# MainBoard1_3.net
KiCad netlist of a schematic drawn in EAGLE
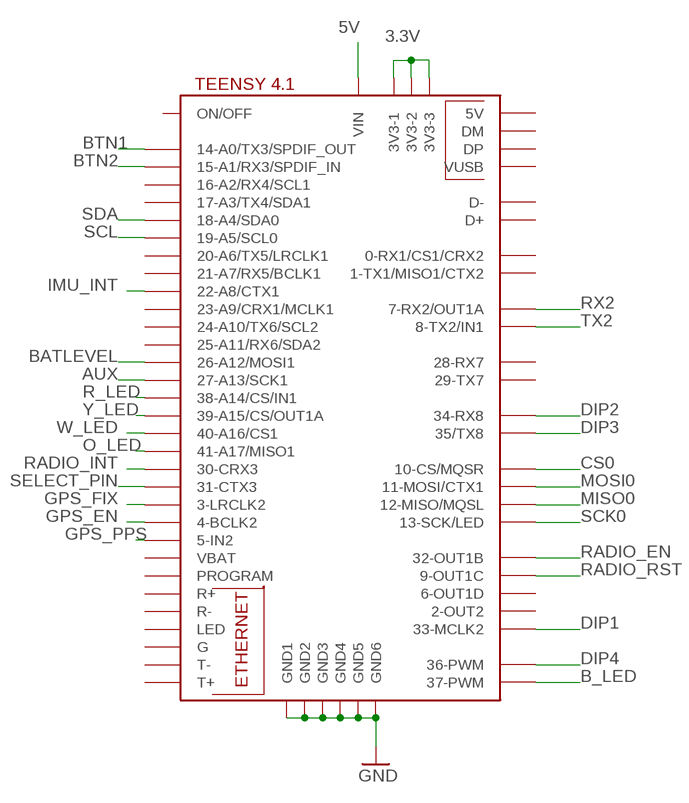
[diagram p0: schematic, sheet 1]
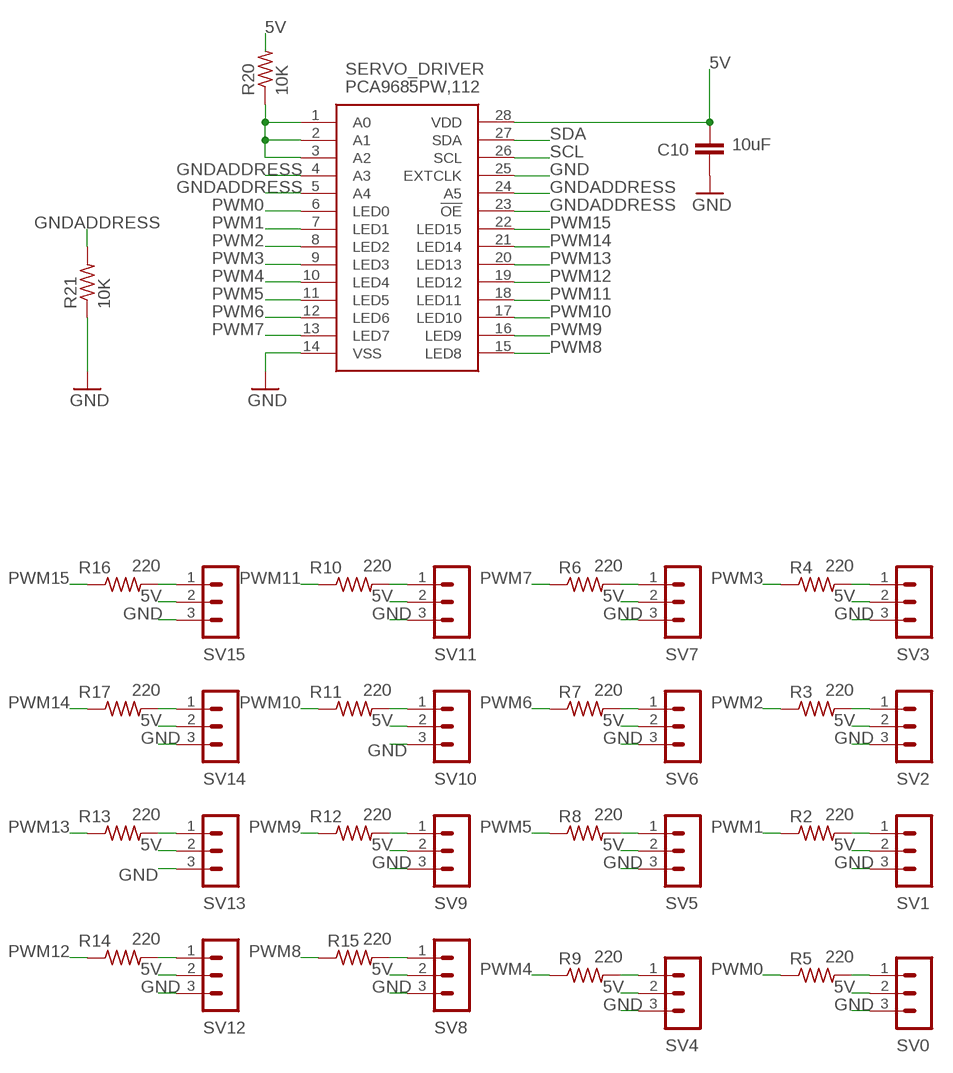
[diagram p1: schematic, sheet 2]
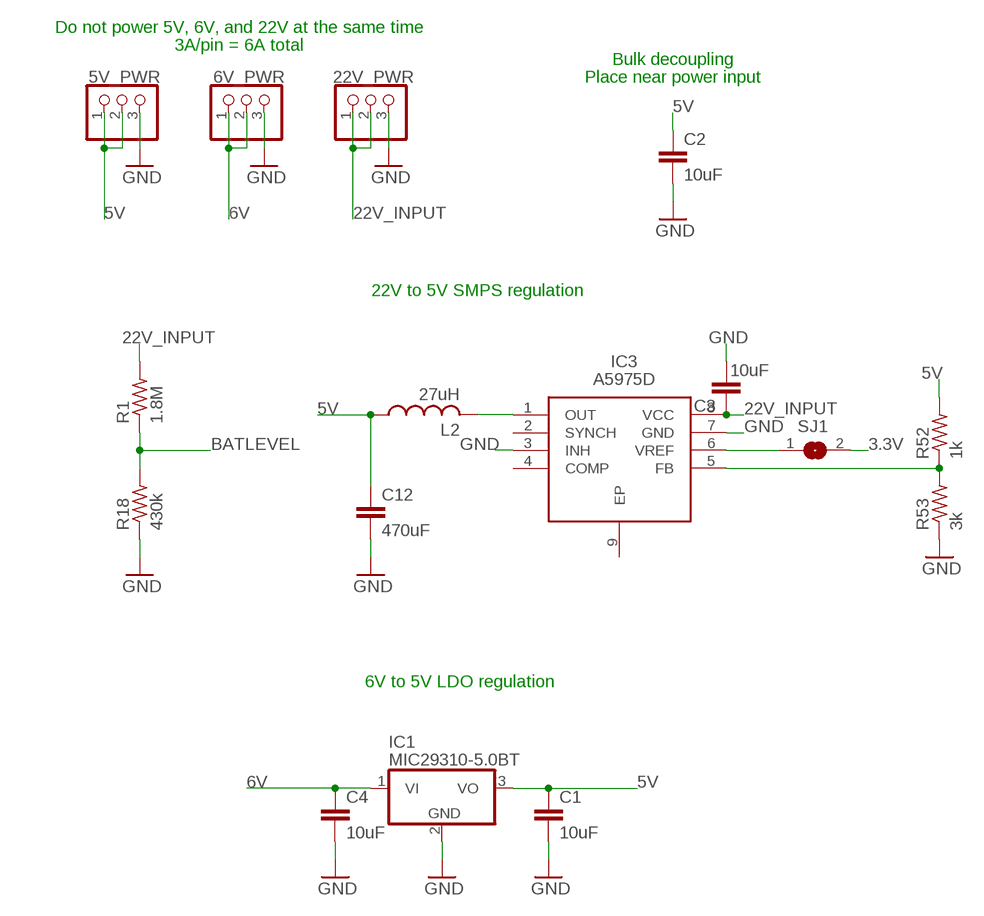
[diagram p2: schematic, sheet 3]
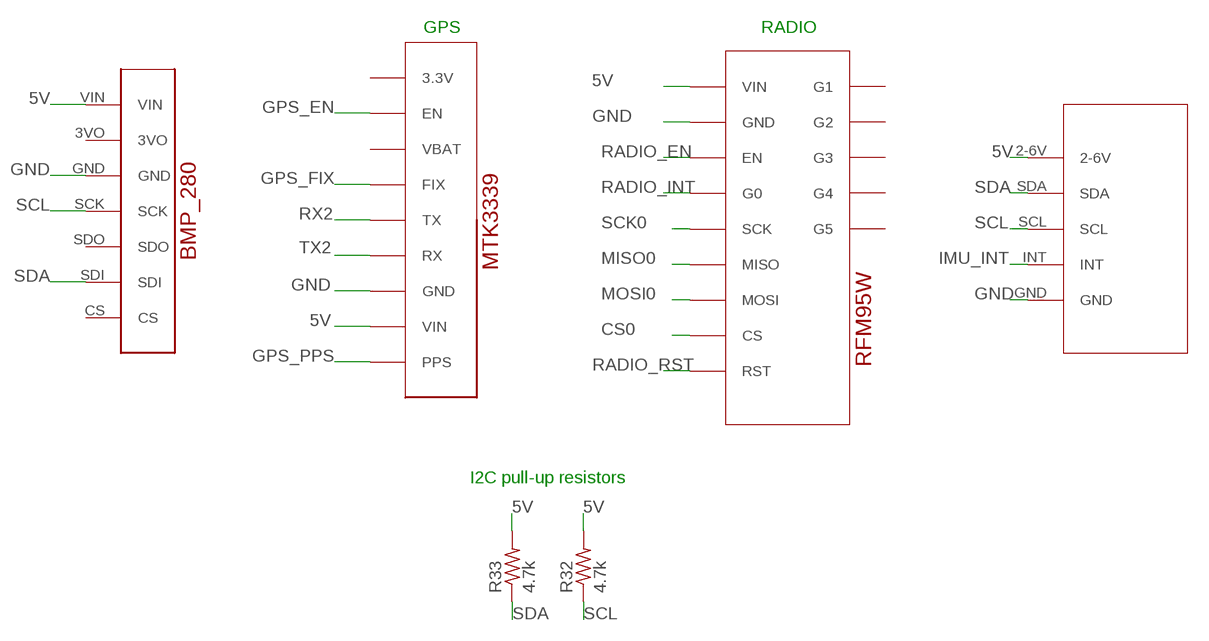
[diagram p3: schematic, sheet 4]
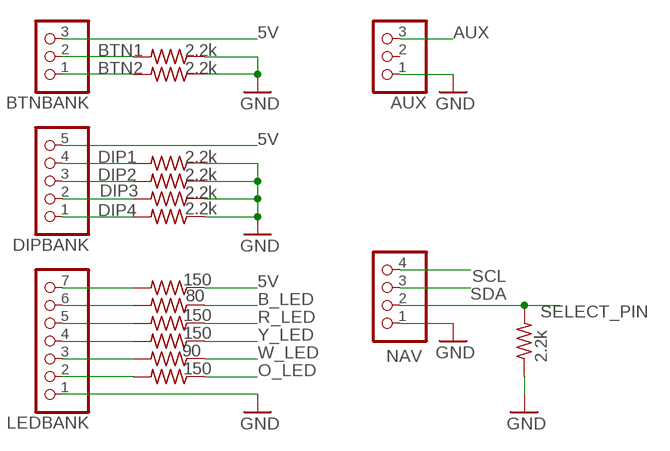
[diagram p4: schematic, sheet 5]
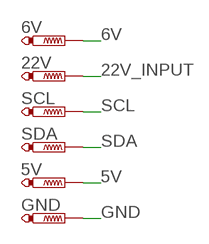
[diagram p5: schematic, sheet 6]

(export (version "E")
  (design (tool "Eeschema 10.0.6"))
  (components
    (comp (ref "5V")
      (value "PTR1B1,27")
      (footprint "eagle-import:B1,27")
      (libsource (lib "eagle-import") (part "PTR1B1,27"))
    )
    (comp (ref "6V")
      (value "PTR1B1,27")
      (footprint "eagle-import:B1,27")
      (libsource (lib "eagle-import") (part "PTR1B1,27"))
    )
    (comp (ref "22V")
      (value "PTR1B1,27")
      (footprint "eagle-import:B1,27")
      (libsource (lib "eagle-import") (part "PTR1B1,27"))
    )
    (comp (ref "GND")
      (value "PTR1B1,27")
      (footprint "eagle-import:B1,27")
      (libsource (lib "eagle-import") (part "PTR1B1,27"))
    )
    (comp (ref "SCL")
      (value "PTR1B1,27")
      (footprint "eagle-import:B1,27")
      (libsource (lib "eagle-import") (part "PTR1B1,27"))
    )
    (comp (ref "SDA")
      (value "PTR1B1,27")
      (footprint "eagle-import:B1,27")
      (libsource (lib "eagle-import") (part "PTR1B1,27"))
    )
    (comp (ref "C10")
      (value "10uF")
      (footprint "eagle-import:C2.5-3")
      (libsource (lib "eagle-import") (part "C2,5-3"))
    )
    (comp (ref "R2")
      (value "220")
      (footprint "eagle-import:0204_7")
      (libsource (lib "eagle-import") (part "R-US_0204/7"))
    )
    (comp (ref "R3")
      (value "220")
      (footprint "eagle-import:0204_7")
      (libsource (lib "eagle-import") (part "R-US_0204/7"))
    )
    (comp (ref "R4")
      (value "220")
      (footprint "eagle-import:0204_7")
      (libsource (lib "eagle-import") (part "R-US_0204/7"))
    )
    (comp (ref "R5")
      (value "220")
      (footprint "eagle-import:0204_7")
      (libsource (lib "eagle-import") (part "R-US_0204/7"))
    )
    (comp (ref "R6")
      (value "220")
      (footprint "eagle-import:0204_7")
      (libsource (lib "eagle-import") (part "R-US_0204/7"))
    )
    (comp (ref "R7")
      (value "220")
      (footprint "eagle-import:0204_7")
      (libsource (lib "eagle-import") (part "R-US_0204/7"))
    )
    (comp (ref "R8")
      (value "220")
      (footprint "eagle-import:0204_7")
      (libsource (lib "eagle-import") (part "R-US_0204/7"))
    )
    (comp (ref "R9")
      (value "220")
      (footprint "eagle-import:0204_7")
      (libsource (lib "eagle-import") (part "R-US_0204/7"))
    )
    (comp (ref "R10")
      (value "220")
      (footprint "eagle-import:0204_7")
      (libsource (lib "eagle-import") (part "R-US_0204/7"))
    )
    (comp (ref "R11")
      (value "220")
      (footprint "eagle-import:0204_7")
      (libsource (lib "eagle-import") (part "R-US_0204/7"))
    )
    (comp (ref "R12")
      (value "220")
      (footprint "eagle-import:0204_7")
      (libsource (lib "eagle-import") (part "R-US_0204/7"))
    )
    (comp (ref "R13")
      (value "220")
      (footprint "eagle-import:0204_7")
      (libsource (lib "eagle-import") (part "R-US_0204/7"))
    )
    (comp (ref "R14")
      (value "220")
      (footprint "eagle-import:0204_7")
      (libsource (lib "eagle-import") (part "R-US_0204/7"))
    )
    (comp (ref "R15")
      (value "220")
      (footprint "eagle-import:0204_7")
      (libsource (lib "eagle-import") (part "R-US_0204/7"))
    )
    (comp (ref "R16")
      (value "220")
      (footprint "eagle-import:0204_7")
      (libsource (lib "eagle-import") (part "R-US_0204/7"))
    )
    (comp (ref "R17")
      (value "220")
      (footprint "eagle-import:0204_7")
      (libsource (lib "eagle-import") (part "R-US_0204/7"))
    )
    (comp (ref "R20")
      (value "10K")
      (footprint "eagle-import:0204_7")
      (libsource (lib "eagle-import") (part "R-US_0204/7"))
    )
    (comp (ref "R21")
      (value "10K")
      (footprint "eagle-import:0204_7")
      (libsource (lib "eagle-import") (part "R-US_0204/7"))
    )
    (comp (ref "SERVO_DRIVER")
      (value "PCA9685PW,112")
      (footprint "eagle-import:SOP65P640X110-28N")
      (fields (field (name "MOUSER_PART_NUMBER") "771-PCA9685PW,112"))
      (libsource (lib "eagle-import") (part "PCA9685PW,112"))
    )
    (comp (ref "SV0")
      (value "MA03-1")
      (footprint "eagle-import:MA03-1")
      (libsource (lib "eagle-import") (part "MA03-1"))
    )
    (comp (ref "SV1")
      (value "MA03-1")
      (footprint "eagle-import:MA03-1")
      (libsource (lib "eagle-import") (part "MA03-1"))
    )
    (comp (ref "SV2")
      (value "MA03-1")
      (footprint "eagle-import:MA03-1")
      (libsource (lib "eagle-import") (part "MA03-1"))
    )
    (comp (ref "SV3")
      (value "MA03-1")
      (footprint "eagle-import:MA03-1")
      (libsource (lib "eagle-import") (part "MA03-1"))
    )
    (comp (ref "SV4")
      (value "MA03-1")
      (footprint "eagle-import:MA03-1")
      (libsource (lib "eagle-import") (part "MA03-1"))
    )
    (comp (ref "SV5")
      (value "MA03-1")
      (footprint "eagle-import:MA03-1")
      (libsource (lib "eagle-import") (part "MA03-1"))
    )
    (comp (ref "SV6")
      (value "MA03-1")
      (footprint "eagle-import:MA03-1")
      (libsource (lib "eagle-import") (part "MA03-1"))
    )
    (comp (ref "SV7")
      (value "MA03-1")
      (footprint "eagle-import:MA03-1")
      (libsource (lib "eagle-import") (part "MA03-1"))
    )
    (comp (ref "SV8")
      (value "MA03-1")
      (footprint "eagle-import:MA03-1")
      (libsource (lib "eagle-import") (part "MA03-1"))
    )
    (comp (ref "SV9")
      (value "MA03-1")
      (footprint "eagle-import:MA03-1")
      (libsource (lib "eagle-import") (part "MA03-1"))
    )
    (comp (ref "SV10")
      (value "MA03-1")
      (footprint "eagle-import:MA03-1")
      (libsource (lib "eagle-import") (part "MA03-1"))
    )
    (comp (ref "SV11")
      (value "MA03-1")
      (footprint "eagle-import:MA03-1")
      (libsource (lib "eagle-import") (part "MA03-1"))
    )
    (comp (ref "SV12")
      (value "MA03-1")
      (footprint "eagle-import:MA03-1")
      (libsource (lib "eagle-import") (part "MA03-1"))
    )
    (comp (ref "SV13")
      (value "MA03-1")
      (footprint "eagle-import:MA03-1")
      (libsource (lib "eagle-import") (part "MA03-1"))
    )
    (comp (ref "SV14")
      (value "MA03-1")
      (footprint "eagle-import:MA03-1")
      (libsource (lib "eagle-import") (part "MA03-1"))
    )
    (comp (ref "SV15")
      (value "MA03-1")
      (footprint "eagle-import:MA03-1")
      (libsource (lib "eagle-import") (part "MA03-1"))
    )
    (comp (ref "GPSMTK3339")
      (value "ADAFRUIT_MTK3339_GPS")
      (footprint "eagle-import:ADAFRUIT_MTK3339_GPS")
      (libsource (lib "eagle-import") (part "ADAFRUIT_MTK3339_GPS"))
    )
    (comp (ref "IMU")
      (value "ICM20948BREAKOUTDEVICE")
      (footprint "eagle-import:ICM20948BREAKOUT")
      (fields (field (name "SPICEPREFIX") "X"))
      (libsource (lib "eagle-import") (part "ICM20948BREAKOUTDEVICE"))
    )
    (comp (ref "R32")
      (value "4.7k")
      (footprint "eagle-import:0204_7")
      (libsource (lib "eagle-import") (part "R-US_0204/7"))
    )
    (comp (ref "R33")
      (value "4.7k")
      (footprint "eagle-import:0204_7")
      (libsource (lib "eagle-import") (part "R-US_0204/7"))
    )
    (comp (ref "RADIO")
      (value "ADAFRUIT_RFM95W_LORA_RADIO")
      (footprint "eagle-import:ADAFRUIT_RFM95W_LORA_RADIO")
      (libsource (lib "eagle-import") (part "ADAFRUIT_RFM95W_LORA_RADIO"))
    )
    (comp (ref "U1")
      (value "ADAFRUIT_BMP280_BAROMETER")
      (footprint "eagle-import:ADAFRUIT_BMP280_BAROMETER")
      (libsource (lib "eagle-import") (part "ADAFRUIT_BMP280_BAROMETER"))
    )
    (comp (ref "5V_PWR")
      (value "5V_PWR")
      (footprint "eagle-import:1X03")
      (libsource (lib "eagle-import") (part "PINHD-1X3"))
    )
    (comp (ref "6V_PWR")
      (value "6V_PWR")
      (footprint "eagle-import:1X03")
      (libsource (lib "eagle-import") (part "PINHD-1X3"))
    )
    (comp (ref "22V_PWR")
      (value "22V_PWR")
      (footprint "eagle-import:1X03")
      (libsource (lib "eagle-import") (part "PINHD-1X3"))
    )
    (comp (ref "C1")
      (value "10uF")
      (footprint "eagle-import:C2.5-3")
      (libsource (lib "eagle-import") (part "C2,5-3"))
    )
    (comp (ref "C2")
      (value "10uF")
      (footprint "eagle-import:C2.5-3")
      (libsource (lib "eagle-import") (part "C2,5-3"))
    )
    (comp (ref "C3")
      (value "10uF")
      (footprint "eagle-import:C2.5-3")
      (libsource (lib "eagle-import") (part "C2,5-3"))
    )
    (comp (ref "C4")
      (value "10uF")
      (footprint "eagle-import:C2.5-3")
      (libsource (lib "eagle-import") (part "C2,5-3"))
    )
    (comp (ref "C12")
      (value "470uF")
      (footprint "eagle-import:C2.5-3")
      (libsource (lib "eagle-import") (part "C2,5-3"))
    )
    (comp (ref "IC1")
      (value "MIC29310-5.0BT")
      (footprint "eagle-import:TO220V")
      (libsource (lib "eagle-import") (part "78TV6"))
    )
    (comp (ref "IC3")
      (value "A5975D")
      (footprint "eagle-import:SOIC127P600X170-9N")
      (fields (field (name "MOUSER_PART_NUMBER") "511-A5975D"))
      (libsource (lib "eagle-import") (part "A5975D"))
    )
    (comp (ref "L2")
      (value "27uH")
      (footprint "eagle-import:TFI0307")
      (libsource (lib "eagle-import") (part "L-USTFI0307"))
    )
    (comp (ref "R1")
      (value "1.8M")
      (footprint "eagle-import:0204_7")
      (libsource (lib "eagle-import") (part "R-US_0204/7"))
    )
    (comp (ref "R18")
      (value "430k")
      (footprint "eagle-import:0204_7")
      (libsource (lib "eagle-import") (part "R-US_0204/7"))
    )
    (comp (ref "R52")
      (value "1k")
      (footprint "eagle-import:0204_7")
      (libsource (lib "eagle-import") (part "R-US_0204/7"))
    )
    (comp (ref "R53")
      (value "3k")
      (footprint "eagle-import:0204_7")
      (libsource (lib "eagle-import") (part "R-US_0204/7"))
    )
    (comp (ref "SJ1") (value "SJ") (footprint "eagle-import:SJ") (libsource (lib "eagle-import") (part "SJ")))
    (comp (ref "AUX")
      (value "PINHD-1X3")
      (footprint "eagle-import:1X03")
      (libsource (lib "eagle-import") (part "PINHD-1X3"))
    )
    (comp (ref "BLUE")
      (value "80")
      (footprint "eagle-import:0204_7")
      (libsource (lib "eagle-import") (part "R-US_0204/7"))
    )
    (comp (ref "BTNBANK")
      (value "PINHD-1X3")
      (footprint "eagle-import:1X03")
      (libsource (lib "eagle-import") (part "PINHD-1X3"))
    )
    (comp (ref "DIPBANK")
      (value "PINHD-1X5")
      (footprint "eagle-import:1X05")
      (libsource (lib "eagle-import") (part "PINHD-1X5"))
    )
    (comp (ref "GREEN")
      (value "150")
      (footprint "eagle-import:0204_7")
      (libsource (lib "eagle-import") (part "R-US_0204/7"))
    )
    (comp (ref "LEDBANK")
      (value "PINHD-1X7")
      (footprint "eagle-import:1X07")
      (libsource (lib "eagle-import") (part "PINHD-1X7"))
    )
    (comp (ref "NAV")
      (value "PINHD-1X4")
      (footprint "eagle-import:1X04")
      (libsource (lib "eagle-import") (part "PINHD-1X4"))
    )
    (comp (ref "ORANGE")
      (value "150")
      (footprint "eagle-import:0204_7")
      (libsource (lib "eagle-import") (part "R-US_0204/7"))
    )
    (comp (ref "R19")
      (value "2.2k")
      (footprint "eagle-import:0204_7")
      (libsource (lib "eagle-import") (part "R-US_0204/7"))
    )
    (comp (ref "R22")
      (value "2.2k")
      (footprint "eagle-import:0204_7")
      (libsource (lib "eagle-import") (part "R-US_0204/7"))
    )
    (comp (ref "R23")
      (value "2.2k")
      (footprint "eagle-import:0204_7")
      (libsource (lib "eagle-import") (part "R-US_0204/7"))
    )
    (comp (ref "R34")
      (value "2.2k")
      (footprint "eagle-import:0204_7")
      (libsource (lib "eagle-import") (part "R-US_0204/7"))
    )
    (comp (ref "R35")
      (value "2.2k")
      (footprint "eagle-import:0204_7")
      (libsource (lib "eagle-import") (part "R-US_0204/7"))
    )
    (comp (ref "R36")
      (value "2.2k")
      (footprint "eagle-import:0204_7")
      (libsource (lib "eagle-import") (part "R-US_0204/7"))
    )
    (comp (ref "R37")
      (value "2.2k")
      (footprint "eagle-import:0204_7")
      (libsource (lib "eagle-import") (part "R-US_0204/7"))
    )
    (comp (ref "RED")
      (value "150")
      (footprint "eagle-import:0204_7")
      (libsource (lib "eagle-import") (part "R-US_0204/7"))
    )
    (comp (ref "WHITE")
      (value "90")
      (footprint "eagle-import:0204_7")
      (libsource (lib "eagle-import") (part "R-US_0204/7"))
    )
    (comp (ref "YELLOW")
      (value "150")
      (footprint "eagle-import:0204_7")
      (libsource (lib "eagle-import") (part "R-US_0204/7"))
    )
    (comp (ref "TEENSY4.1")
      (value "TEENSY41")
      (footprint "eagle-import:TEENSY41")
      (libsource (lib "eagle-import") (part "TEENSY41"))
    )
  )
  (nets
    (net (code "1") (name "3.3V") (class "Default")
      (node (ref "SJ1") (pin "2") (pinfunction "2_2") (pintype "passive"))
      (node (ref "TEENSY4.1") (pin "3V3-1") (pinfunction "3V3-1_3V3-1") (pintype "bidirectional"))
      (node (ref "TEENSY4.1") (pin "3V3-2") (pinfunction "3V3-2_3V3-2") (pintype "bidirectional"))
      (node (ref "TEENSY4.1") (pin "3V3-3") (pinfunction "3V3-3_3V3-3") (pintype "bidirectional"))
    )
    (net (code "2") (name "5V") (class "Default")
      (node (ref "5V") (pin "TP") (pinfunction "TP_TP") (pintype "input"))
      (node (ref "5V_PWR") (pin "1") (pinfunction "1_1") (pintype "passive"))
      (node (ref "5V_PWR") (pin "2") (pinfunction "2_2") (pintype "passive"))
      (node (ref "BTNBANK") (pin "3") (pinfunction "3_3") (pintype "passive"))
      (node (ref "C1") (pin "1") (pinfunction "1_1") (pintype "passive"))
      (node (ref "C10") (pin "1") (pinfunction "1_1") (pintype "passive"))
      (node (ref "C12") (pin "1") (pinfunction "1_1") (pintype "passive"))
      (node (ref "C2") (pin "1") (pinfunction "1_1") (pintype "passive"))
      (node (ref "DIPBANK") (pin "5") (pinfunction "5_5") (pintype "passive"))
      (node (ref "GPSMTK3339") (pin "VIN") (pinfunction "VIN_VIN") (pintype "bidirectional"))
      (node (ref "GREEN") (pin "1") (pinfunction "1_1") (pintype "passive"))
      (node (ref "IC1") (pin "3") (pinfunction "VO_3") (pintype "passive"))
      (node (ref "IMU") (pin "2-6V") (pinfunction "2-6V_2-6V") (pintype "bidirectional"))
      (node (ref "L2") (pin "1") (pinfunction "1_1") (pintype "passive"))
      (node (ref "R20") (pin "2") (pinfunction "2_2") (pintype "passive"))
      (node (ref "R32") (pin "2") (pinfunction "2_2") (pintype "passive"))
      (node (ref "R33") (pin "2") (pinfunction "2_2") (pintype "passive"))
      (node (ref "R52") (pin "2") (pinfunction "2_2") (pintype "passive"))
      (node (ref "RADIO") (pin "1") (pinfunction "VIN_1") (pintype "bidirectional"))
      (node (ref "SERVO_DRIVER") (pin "28") (pinfunction "VDD_28") (pintype "bidirectional"))
      (node (ref "SV0") (pin "2") (pinfunction "2_2") (pintype "passive"))
      (node (ref "SV1") (pin "2") (pinfunction "2_2") (pintype "passive"))
      (node (ref "SV10") (pin "2") (pinfunction "2_2") (pintype "passive"))
      (node (ref "SV11") (pin "2") (pinfunction "2_2") (pintype "passive"))
      (node (ref "SV12") (pin "2") (pinfunction "2_2") (pintype "passive"))
      (node (ref "SV13") (pin "2") (pinfunction "2_2") (pintype "passive"))
      (node (ref "SV14") (pin "2") (pinfunction "2_2") (pintype "passive"))
      (node (ref "SV15") (pin "2") (pinfunction "2_2") (pintype "passive"))
      (node (ref "SV2") (pin "2") (pinfunction "2_2") (pintype "passive"))
      (node (ref "SV3") (pin "2") (pinfunction "2_2") (pintype "passive"))
      (node (ref "SV4") (pin "2") (pinfunction "2_2") (pintype "passive"))
      (node (ref "SV5") (pin "2") (pinfunction "2_2") (pintype "passive"))
      (node (ref "SV6") (pin "2") (pinfunction "2_2") (pintype "passive"))
      (node (ref "SV7") (pin "2") (pinfunction "2_2") (pintype "passive"))
      (node (ref "SV8") (pin "2") (pinfunction "2_2") (pintype "passive"))
      (node (ref "SV9") (pin "2") (pinfunction "2_2") (pintype "passive"))
      (node (ref "TEENSY4.1") (pin "VIN") (pinfunction "VIN_VIN") (pintype "bidirectional"))
      (node (ref "U1") (pin "VIN") (pinfunction "VIN_VIN") (pintype "bidirectional"))
    )
    (net (code "3") (name "6V") (class "Default")
      (node (ref "6V") (pin "TP") (pinfunction "TP_TP") (pintype "input"))
      (node (ref "6V_PWR") (pin "1") (pinfunction "1_1") (pintype "passive"))
      (node (ref "6V_PWR") (pin "2") (pinfunction "2_2") (pintype "passive"))
      (node (ref "C4") (pin "1") (pinfunction "1_1") (pintype "passive"))
      (node (ref "IC1") (pin "1") (pinfunction "VI_1") (pintype "input"))
    )
    (net (code "4") (name "22V_INPUT") (class "Default")
      (node (ref "22V") (pin "TP") (pinfunction "TP_TP") (pintype "input"))
      (node (ref "22V_PWR") (pin "1") (pinfunction "1_1") (pintype "passive"))
      (node (ref "22V_PWR") (pin "2") (pinfunction "2_2") (pintype "passive"))
      (node (ref "C3") (pin "1") (pinfunction "1_1") (pintype "passive"))
      (node (ref "IC3") (pin "8") (pinfunction "VCC_8") (pintype "bidirectional"))
      (node (ref "R1") (pin "2") (pinfunction "2_2") (pintype "passive"))
    )
    (net (code "5") (name "AUX") (class "Default")
      (node (ref "AUX") (pin "3") (pinfunction "3_3") (pintype "passive"))
      (node (ref "TEENSY4.1") (pin "27-A13/SCK1") (pinfunction "27-A13/SCK1_27-A13/SCK1") (pintype "bidirectional"))
    )
    (net (code "6") (name "BATLEVEL") (class "Default")
      (node (ref "R1") (pin "1") (pinfunction "1_1") (pintype "passive"))
      (node (ref "R18") (pin "2") (pinfunction "2_2") (pintype "passive"))
      (node (ref "TEENSY4.1") (pin "26-A12/MOSI1") (pinfunction "26-A12/MOSI1_26-A12/MOSI1") (pintype "bidirectional"))
    )
    (net (code "7") (name "BTN1") (class "Default")
      (node (ref "BTNBANK") (pin "2") (pinfunction "2_2") (pintype "passive"))
      (node (ref "R19") (pin "2") (pinfunction "2_2") (pintype "passive"))
      (node (ref "TEENSY4.1") (pin "14-A0/TX3/SPDIF_OUT") (pinfunction "14-A0/TX3/SPDIF_OUT_14-A0/TX3/SPDIF_OUT") (pintype "bidirectional"))
    )
    (net (code "8") (name "BTN2") (class "Default")
      (node (ref "BTNBANK") (pin "1") (pinfunction "1_1") (pintype "passive"))
      (node (ref "R22") (pin "2") (pinfunction "2_2") (pintype "passive"))
      (node (ref "TEENSY4.1") (pin "15-A1/RX3/SPDIF_IN") (pinfunction "15-A1/RX3/SPDIF_IN_15-A1/RX3/SPDIF_IN") (pintype "bidirectional"))
    )
    (net (code "9") (name "B_LED") (class "Default")
      (node (ref "BLUE") (pin "1") (pinfunction "1_1") (pintype "passive"))
      (node (ref "TEENSY4.1") (pin "37-PWM") (pinfunction "37-PWM_37-PWM") (pintype "bidirectional"))
    )
    (net (code "10") (name "CS0") (class "Default")
      (node (ref "RADIO") (pin "8") (pinfunction "CS_8") (pintype "bidirectional"))
      (node (ref "TEENSY4.1") (pin "10-CS\\MQSR") (pinfunction "10-CS/MQSR_10-CS\\MQSR") (pintype "bidirectional"))
    )
    (net (code "11") (name "DIP1") (class "Default")
      (node (ref "DIPBANK") (pin "4") (pinfunction "4_4") (pintype "passive"))
      (node (ref "R37") (pin "2") (pinfunction "2_2") (pintype "passive"))
      (node (ref "TEENSY4.1") (pin "33-MCLK2") (pinfunction "33-MCLK2_33-MCLK2") (pintype "bidirectional"))
    )
    (net (code "12") (name "DIP2") (class "Default")
      (node (ref "DIPBANK") (pin "3") (pinfunction "3_3") (pintype "passive"))
      (node (ref "R36") (pin "2") (pinfunction "2_2") (pintype "passive"))
      (node (ref "TEENSY4.1") (pin "34-RX8") (pinfunction "34-RX8_34-RX8") (pintype "bidirectional"))
    )
    (net (code "13") (name "DIP3") (class "Default")
      (node (ref "DIPBANK") (pin "2") (pinfunction "2_2") (pintype "passive"))
      (node (ref "R34") (pin "2") (pinfunction "2_2") (pintype "passive"))
      (node (ref "TEENSY4.1") (pin "35-TX8") (pinfunction "35/TX8_35-TX8") (pintype "bidirectional"))
    )
    (net (code "14") (name "DIP4") (class "Default")
      (node (ref "DIPBANK") (pin "1") (pinfunction "1_1") (pintype "passive"))
      (node (ref "R35") (pin "2") (pinfunction "2_2") (pintype "passive"))
      (node (ref "TEENSY4.1") (pin "36-PWM") (pinfunction "36-PWM_36-PWM") (pintype "bidirectional"))
    )
    (net (code "15") (name "GND") (class "Default")
      (node (ref "22V_PWR") (pin "3") (pinfunction "3_3") (pintype "passive"))
      (node (ref "5V_PWR") (pin "3") (pinfunction "3_3") (pintype "passive"))
      (node (ref "6V_PWR") (pin "3") (pinfunction "3_3") (pintype "passive"))
      (node (ref "AUX") (pin "1") (pinfunction "1_1") (pintype "passive"))
      (node (ref "C1") (pin "2") (pinfunction "2_2") (pintype "passive"))
      (node (ref "C10") (pin "2") (pinfunction "2_2") (pintype "passive"))
      (node (ref "C12") (pin "2") (pinfunction "2_2") (pintype "passive"))
      (node (ref "C2") (pin "2") (pinfunction "2_2") (pintype "passive"))
      (node (ref "C3") (pin "2") (pinfunction "2_2") (pintype "passive"))
      (node (ref "C4") (pin "2") (pinfunction "2_2") (pintype "passive"))
      (node (ref "GND") (pin "TP") (pinfunction "TP_TP") (pintype "input"))
      (node (ref "GPSMTK3339") (pin "GND") (pinfunction "GND_GND") (pintype "bidirectional"))
      (node (ref "IC1") (pin "2") (pinfunction "GND_2") (pintype "passive"))
      (node (ref "IC3") (pin "3") (pinfunction "INH_3") (pintype "bidirectional"))
      (node (ref "IC3") (pin "7") (pinfunction "GND_7") (pintype "bidirectional"))
      (node (ref "IMU") (pin "GND") (pinfunction "GND_GND") (pintype "bidirectional"))
      (node (ref "LEDBANK") (pin "1") (pinfunction "1_1") (pintype "passive"))
      (node (ref "NAV") (pin "1") (pinfunction "1_1") (pintype "passive"))
      (node (ref "R18") (pin "1") (pinfunction "1_1") (pintype "passive"))
      (node (ref "R19") (pin "1") (pinfunction "1_1") (pintype "passive"))
      (node (ref "R21") (pin "1") (pinfunction "1_1") (pintype "passive"))
      (node (ref "R22") (pin "1") (pinfunction "1_1") (pintype "passive"))
      (node (ref "R23") (pin "1") (pinfunction "1_1") (pintype "passive"))
      (node (ref "R34") (pin "1") (pinfunction "1_1") (pintype "passive"))
      (node (ref "R35") (pin "1") (pinfunction "1_1") (pintype "passive"))
      (node (ref "R36") (pin "1") (pinfunction "1_1") (pintype "passive"))
      (node (ref "R37") (pin "1") (pinfunction "1_1") (pintype "passive"))
      (node (ref "R53") (pin "1") (pinfunction "1_1") (pintype "passive"))
      (node (ref "RADIO") (pin "2") (pinfunction "GND_2") (pintype "bidirectional"))
      (node (ref "SERVO_DRIVER") (pin "14") (pinfunction "VSS_14") (pintype "bidirectional"))
      (node (ref "SERVO_DRIVER") (pin "25") (pinfunction "EXTCLK_25") (pintype "bidirectional"))
      (node (ref "SV0") (pin "3") (pinfunction "3_3") (pintype "passive"))
      (node (ref "SV1") (pin "3") (pinfunction "3_3") (pintype "passive"))
      (node (ref "SV10") (pin "3") (pinfunction "3_3") (pintype "passive"))
      (node (ref "SV11") (pin "3") (pinfunction "3_3") (pintype "passive"))
      (node (ref "SV12") (pin "3") (pinfunction "3_3") (pintype "passive"))
      (node (ref "SV13") (pin "3") (pinfunction "3_3") (pintype "passive"))
      (node (ref "SV14") (pin "3") (pinfunction "3_3") (pintype "passive"))
      (node (ref "SV15") (pin "3") (pinfunction "3_3") (pintype "passive"))
      (node (ref "SV2") (pin "3") (pinfunction "3_3") (pintype "passive"))
      (node (ref "SV3") (pin "3") (pinfunction "3_3") (pintype "passive"))
      (node (ref "SV4") (pin "3") (pinfunction "3_3") (pintype "passive"))
      (node (ref "SV5") (pin "3") (pinfunction "3_3") (pintype "passive"))
      (node (ref "SV6") (pin "3") (pinfunction "3_3") (pintype "passive"))
      (node (ref "SV7") (pin "3") (pinfunction "3_3") (pintype "passive"))
      (node (ref "SV8") (pin "3") (pinfunction "3_3") (pintype "passive"))
      (node (ref "SV9") (pin "3") (pinfunction "3_3") (pintype "passive"))
      (node (ref "TEENSY4.1") (pin "GND1") (pinfunction "GND1_GND1") (pintype "bidirectional"))
      (node (ref "TEENSY4.1") (pin "GND2") (pinfunction "GND2_GND2") (pintype "bidirectional"))
      (node (ref "TEENSY4.1") (pin "GND3") (pinfunction "GND3_GND3") (pintype "bidirectional"))
      (node (ref "TEENSY4.1") (pin "GND4") (pinfunction "GND4_GND4") (pintype "bidirectional"))
      (node (ref "TEENSY4.1") (pin "GND5") (pinfunction "GND5_GND5") (pintype "bidirectional"))
      (node (ref "TEENSY4.1") (pin "GND6") (pinfunction "GND6_GND6") (pintype "bidirectional"))
      (node (ref "U1") (pin "GND") (pinfunction "GND_GND") (pintype "bidirectional"))
    )
    (net (code "16") (name "GNDADDRESS") (class "Default")
      (node (ref "R21") (pin "2") (pinfunction "2_2") (pintype "passive"))
      (node (ref "SERVO_DRIVER") (pin "23") (pinfunction "~{OE}_23") (pintype "bidirectional"))
      (node (ref "SERVO_DRIVER") (pin "24") (pinfunction "A5_24") (pintype "bidirectional"))
      (node (ref "SERVO_DRIVER") (pin "4") (pinfunction "A3_4") (pintype "bidirectional"))
      (node (ref "SERVO_DRIVER") (pin "5") (pinfunction "A4_5") (pintype "bidirectional"))
    )
    (net (code "17") (name "GPS_EN") (class "Default")
      (node (ref "GPSMTK3339") (pin "EN") (pinfunction "EN_EN") (pintype "bidirectional"))
      (node (ref "TEENSY4.1") (pin "4-BCLK2") (pinfunction "4-BCLK2_4-BCLK2") (pintype "bidirectional"))
    )
    (net (code "18") (name "GPS_FIX") (class "Default")
      (node (ref "GPSMTK3339") (pin "FIX") (pinfunction "FIX_FIX") (pintype "bidirectional"))
      (node (ref "TEENSY4.1") (pin "3-LRCLK2") (pinfunction "3-LRCLK2_3-LRCLK2") (pintype "bidirectional"))
    )
    (net (code "19") (name "GPS_PPS") (class "Default")
      (node (ref "GPSMTK3339") (pin "PPS") (pinfunction "PPS_PPS") (pintype "bidirectional"))
      (node (ref "TEENSY4.1") (pin "5-IN2") (pinfunction "5-IN2_5-IN2") (pintype "bidirectional"))
    )
    (net (code "20") (name "IMU_INT") (class "Default")
      (node (ref "IMU") (pin "INT") (pinfunction "INT_INT") (pintype "bidirectional"))
      (node (ref "TEENSY4.1") (pin "22-A8/CTX1") (pinfunction "22-A8/CTX1_22-A8/CTX1") (pintype "bidirectional"))
    )
    (net (code "21") (name "MISO0") (class "Default")
      (node (ref "RADIO") (pin "6") (pinfunction "MISO_6") (pintype "bidirectional"))
      (node (ref "TEENSY4.1") (pin "12-MISO/MQSL") (pinfunction "12-MISO/MQSL_12-MISO/MQSL") (pintype "bidirectional"))
    )
    (net (code "22") (name "MOSI0") (class "Default")
      (node (ref "RADIO") (pin "7") (pinfunction "MOSI_7") (pintype "bidirectional"))
      (node (ref "TEENSY4.1") (pin "11-MOSI/CTX1") (pinfunction "11-MOSI/CTX1_11-MOSI/CTX1") (pintype "bidirectional"))
    )
    (net (code "23") (name "Net-(BLUE-Pad2)") (class "Default")
      (node (ref "BLUE") (pin "2") (pinfunction "2_2") (pintype "passive"))
      (node (ref "LEDBANK") (pin "6") (pinfunction "6_6") (pintype "passive"))
    )
    (net (code "24") (name "Net-(GREEN-Pad2)") (class "Default")
      (node (ref "GREEN") (pin "2") (pinfunction "2_2") (pintype "passive"))
      (node (ref "LEDBANK") (pin "7") (pinfunction "7_7") (pintype "passive"))
    )
    (net (code "25") (name "Net-(IC3-FB)") (class "Default")
      (node (ref "IC3") (pin "5") (pinfunction "FB_5") (pintype "bidirectional"))
      (node (ref "R52") (pin "1") (pinfunction "1_1") (pintype "passive"))
      (node (ref "R53") (pin "2") (pinfunction "2_2") (pintype "passive"))
    )
    (net (code "26") (name "Net-(IC3-OUT)") (class "Default")
      (node (ref "IC3") (pin "1") (pinfunction "OUT_1") (pintype "bidirectional"))
      (node (ref "L2") (pin "2") (pinfunction "2_2") (pintype "passive"))
    )
    (net (code "27") (name "Net-(IC3-VREF)") (class "Default")
      (node (ref "IC3") (pin "6") (pinfunction "VREF_6") (pintype "bidirectional"))
      (node (ref "SJ1") (pin "1") (pinfunction "1_1") (pintype "passive"))
    )
    (net (code "28") (name "Net-(LEDBANK-Pad2)") (class "Default")
      (node (ref "LEDBANK") (pin "2") (pinfunction "2_2") (pintype "passive"))
      (node (ref "ORANGE") (pin "2") (pinfunction "2_2") (pintype "passive"))
    )
    (net (code "29") (name "Net-(LEDBANK-Pad3)") (class "Default")
      (node (ref "LEDBANK") (pin "3") (pinfunction "3_3") (pintype "passive"))
      (node (ref "WHITE") (pin "2") (pinfunction "2_2") (pintype "passive"))
    )
    (net (code "30") (name "Net-(LEDBANK-Pad4)") (class "Default")
      (node (ref "LEDBANK") (pin "4") (pinfunction "4_4") (pintype "passive"))
      (node (ref "YELLOW") (pin "2") (pinfunction "2_2") (pintype "passive"))
    )
    (net (code "31") (name "Net-(LEDBANK-Pad5)") (class "Default")
      (node (ref "LEDBANK") (pin "5") (pinfunction "5_5") (pintype "passive"))
      (node (ref "RED") (pin "2") (pinfunction "2_2") (pintype "passive"))
    )
    (net (code "32") (name "Net-(R2-Pad2)") (class "Default")
      (node (ref "R2") (pin "2") (pinfunction "2_2") (pintype "passive"))
      (node (ref "SV1") (pin "1") (pinfunction "1_1") (pintype "passive"))
    )
    (net (code "33") (name "Net-(R3-Pad2)") (class "Default")
      (node (ref "R3") (pin "2") (pinfunction "2_2") (pintype "passive"))
      (node (ref "SV2") (pin "1") (pinfunction "1_1") (pintype "passive"))
    )
    (net (code "34") (name "Net-(R4-Pad2)") (class "Default")
      (node (ref "R4") (pin "2") (pinfunction "2_2") (pintype "passive"))
      (node (ref "SV3") (pin "1") (pinfunction "1_1") (pintype "passive"))
    )
    (net (code "35") (name "Net-(R5-Pad2)") (class "Default")
      (node (ref "R5") (pin "2") (pinfunction "2_2") (pintype "passive"))
      (node (ref "SV0") (pin "1") (pinfunction "1_1") (pintype "passive"))
    )
    (net (code "36") (name "Net-(R6-Pad2)") (class "Default")
      (node (ref "R6") (pin "2") (pinfunction "2_2") (pintype "passive"))
      (node (ref "SV7") (pin "1") (pinfunction "1_1") (pintype "passive"))
    )
    (net (code "37") (name "Net-(R7-Pad2)") (class "Default")
      (node (ref "R7") (pin "2") (pinfunction "2_2") (pintype "passive"))
      (node (ref "SV6") (pin "1") (pinfunction "1_1") (pintype "passive"))
    )
    (net (code "38") (name "Net-(R8-Pad2)") (class "Default")
      (node (ref "R8") (pin "2") (pinfunction "2_2") (pintype "passive"))
      (node (ref "SV5") (pin "1") (pinfunction "1_1") (pintype "passive"))
    )
    (net (code "39") (name "Net-(R9-Pad2)") (class "Default")
      (node (ref "R9") (pin "2") (pinfunction "2_2") (pintype "passive"))
      (node (ref "SV4") (pin "1") (pinfunction "1_1") (pintype "passive"))
    )
    (net (code "40") (name "Net-(R10-Pad2)") (class "Default")
      (node (ref "R10") (pin "2") (pinfunction "2_2") (pintype "passive"))
      (node (ref "SV11") (pin "1") (pinfunction "1_1") (pintype "passive"))
    )
    (net (code "41") (name "Net-(R11-Pad2)") (class "Default")
      (node (ref "R11") (pin "2") (pinfunction "2_2") (pintype "passive"))
      (node (ref "SV10") (pin "1") (pinfunction "1_1") (pintype "passive"))
    )
    (net (code "42") (name "Net-(R12-Pad2)") (class "Default")
      (node (ref "R12") (pin "2") (pinfunction "2_2") (pintype "passive"))
      (node (ref "SV9") (pin "1") (pinfunction "1_1") (pintype "passive"))
    )
    (net (code "43") (name "Net-(R13-Pad2)") (class "Default")
      (node (ref "R13") (pin "2") (pinfunction "2_2") (pintype "passive"))
      (node (ref "SV13") (pin "1") (pinfunction "1_1") (pintype "passive"))
    )
    (net (code "44") (name "Net-(R14-Pad2)") (class "Default")
      (node (ref "R14") (pin "2") (pinfunction "2_2") (pintype "passive"))
      (node (ref "SV12") (pin "1") (pinfunction "1_1") (pintype "passive"))
    )
    (net (code "45") (name "Net-(R15-Pad2)") (class "Default")
      (node (ref "R15") (pin "2") (pinfunction "2_2") (pintype "passive"))
      (node (ref "SV8") (pin "1") (pinfunction "1_1") (pintype "passive"))
    )
    (net (code "46") (name "Net-(R16-Pad2)") (class "Default")
      (node (ref "R16") (pin "2") (pinfunction "2_2") (pintype "passive"))
      (node (ref "SV15") (pin "1") (pinfunction "1_1") (pintype "passive"))
    )
    (net (code "47") (name "Net-(R17-Pad2)") (class "Default")
      (node (ref "R17") (pin "2") (pinfunction "2_2") (pintype "passive"))
      (node (ref "SV14") (pin "1") (pinfunction "1_1") (pintype "passive"))
    )
    (net (code "48") (name "Net-(SERVO_DRIVER-A0)") (class "Default")
      (node (ref "R20") (pin "1") (pinfunction "1_1") (pintype "passive"))
      (node (ref "SERVO_DRIVER") (pin "1") (pinfunction "A0_1") (pintype "bidirectional"))
      (node (ref "SERVO_DRIVER") (pin "2") (pinfunction "A1_2") (pintype "bidirectional"))
      (node (ref "SERVO_DRIVER") (pin "3") (pinfunction "A2_3") (pintype "bidirectional"))
    )
    (net (code "49") (name "O_LED") (class "Default")
      (node (ref "ORANGE") (pin "1") (pinfunction "1_1") (pintype "passive"))
      (node (ref "TEENSY4.1") (pin "41-A17/MISO1") (pinfunction "41-A17/MISO1_41-A17/MISO1") (pintype "bidirectional"))
    )
    (net (code "50") (name "PWM0") (class "Default")
      (node (ref "R5") (pin "1") (pinfunction "1_1") (pintype "passive"))
      (node (ref "SERVO_DRIVER") (pin "6") (pinfunction "LED0_6") (pintype "bidirectional"))
    )
    (net (code "51") (name "PWM1") (class "Default")
      (node (ref "R2") (pin "1") (pinfunction "1_1") (pintype "passive"))
      (node (ref "SERVO_DRIVER") (pin "7") (pinfunction "LED1_7") (pintype "bidirectional"))
    )
    (net (code "52") (name "PWM2") (class "Default")
      (node (ref "R3") (pin "1") (pinfunction "1_1") (pintype "passive"))
      (node (ref "SERVO_DRIVER") (pin "8") (pinfunction "LED2_8") (pintype "bidirectional"))
    )
    (net (code "53") (name "PWM3") (class "Default")
      (node (ref "R4") (pin "1") (pinfunction "1_1") (pintype "passive"))
      (node (ref "SERVO_DRIVER") (pin "9") (pinfunction "LED3_9") (pintype "bidirectional"))
    )
    (net (code "54") (name "PWM4") (class "Default")
      (node (ref "R9") (pin "1") (pinfunction "1_1") (pintype "passive"))
      (node (ref "SERVO_DRIVER") (pin "10") (pinfunction "LED4_10") (pintype "bidirectional"))
    )
    (net (code "55") (name "PWM5") (class "Default")
      (node (ref "R8") (pin "1") (pinfunction "1_1") (pintype "passive"))
      (node (ref "SERVO_DRIVER") (pin "11") (pinfunction "LED5_11") (pintype "bidirectional"))
    )
    (net (code "56") (name "PWM6") (class "Default")
      (node (ref "R7") (pin "1") (pinfunction "1_1") (pintype "passive"))
      (node (ref "SERVO_DRIVER") (pin "12") (pinfunction "LED6_12") (pintype "bidirectional"))
    )
    (net (code "57") (name "PWM7") (class "Default")
      (node (ref "R6") (pin "1") (pinfunction "1_1") (pintype "passive"))
      (node (ref "SERVO_DRIVER") (pin "13") (pinfunction "LED7_13") (pintype "bidirectional"))
    )
    (net (code "58") (name "PWM8") (class "Default")
      (node (ref "R15") (pin "1") (pinfunction "1_1") (pintype "passive"))
      (node (ref "SERVO_DRIVER") (pin "15") (pinfunction "LED8_15") (pintype "bidirectional"))
    )
    (net (code "59") (name "PWM9") (class "Default")
      (node (ref "R12") (pin "1") (pinfunction "1_1") (pintype "passive"))
      (node (ref "SERVO_DRIVER") (pin "16") (pinfunction "LED9_16") (pintype "bidirectional"))
    )
    (net (code "60") (name "PWM10") (class "Default")
      (node (ref "R11") (pin "1") (pinfunction "1_1") (pintype "passive"))
      (node (ref "SERVO_DRIVER") (pin "17") (pinfunction "LED10_17") (pintype "bidirectional"))
    )
    (net (code "61") (name "PWM11") (class "Default")
      (node (ref "R10") (pin "1") (pinfunction "1_1") (pintype "passive"))
      (node (ref "SERVO_DRIVER") (pin "18") (pinfunction "LED11_18") (pintype "bidirectional"))
    )
    (net (code "62") (name "PWM12") (class "Default")
      (node (ref "R14") (pin "1") (pinfunction "1_1") (pintype "passive"))
      (node (ref "SERVO_DRIVER") (pin "19") (pinfunction "LED12_19") (pintype "bidirectional"))
    )
    (net (code "63") (name "PWM13") (class "Default")
      (node (ref "R13") (pin "1") (pinfunction "1_1") (pintype "passive"))
      (node (ref "SERVO_DRIVER") (pin "20") (pinfunction "LED13_20") (pintype "bidirectional"))
    )
    (net (code "64") (name "PWM14") (class "Default")
      (node (ref "R17") (pin "1") (pinfunction "1_1") (pintype "passive"))
      (node (ref "SERVO_DRIVER") (pin "21") (pinfunction "LED14_21") (pintype "bidirectional"))
    )
    (net (code "65") (name "PWM15") (class "Default")
      (node (ref "R16") (pin "1") (pinfunction "1_1") (pintype "passive"))
      (node (ref "SERVO_DRIVER") (pin "22") (pinfunction "LED15_22") (pintype "bidirectional"))
    )
    (net (code "66") (name "RADIO_EN") (class "Default")
      (node (ref "RADIO") (pin "3") (pinfunction "EN_3") (pintype "bidirectional"))
      (node (ref "TEENSY4.1") (pin "32-OUT1B") (pinfunction "32-OUT1B_32-OUT1B") (pintype "bidirectional"))
    )
    (net (code "67") (name "RADIO_INT") (class "Default")
      (node (ref "RADIO") (pin "4") (pinfunction "G0_4") (pintype "bidirectional"))
      (node (ref "TEENSY4.1") (pin "30-CRX3") (pinfunction "30-CRX3_30-CRX3") (pintype "bidirectional"))
    )
    (net (code "68") (name "RADIO_RST") (class "Default")
      (node (ref "RADIO") (pin "9") (pinfunction "RST_9") (pintype "bidirectional"))
      (node (ref "TEENSY4.1") (pin "9-OUT1C") (pinfunction "9-OUT1C_9-OUT1C") (pintype "bidirectional"))
    )
    (net (code "69") (name "RX2") (class "Default")
      (node (ref "GPSMTK3339") (pin "TX") (pinfunction "TX_TX") (pintype "bidirectional"))
      (node (ref "TEENSY4.1") (pin "7-RX2/OUT1A") (pinfunction "7-RX2/OUT1A_7-RX2/OUT1A") (pintype "bidirectional"))
    )
    (net (code "70") (name "R_LED") (class "Default")
      (node (ref "RED") (pin "1") (pinfunction "1_1") (pintype "passive"))
      (node (ref "TEENSY4.1") (pin "38-A14/CS/IN1") (pinfunction "38-A14/CS/IN1_38-A14/CS/IN1") (pintype "bidirectional"))
    )
    (net (code "71") (name "SCK0") (class "Default")
      (node (ref "RADIO") (pin "5") (pinfunction "SCK_5") (pintype "bidirectional"))
      (node (ref "TEENSY4.1") (pin "13-SCK/LED") (pinfunction "13-SCK/LED_13-SCK/LED") (pintype "bidirectional"))
    )
    (net (code "72") (name "SCL") (class "Default")
      (node (ref "IMU") (pin "SCL") (pinfunction "SCL_SCL") (pintype "bidirectional"))
      (node (ref "NAV") (pin "4") (pinfunction "4_4") (pintype "passive"))
      (node (ref "R32") (pin "1") (pinfunction "1_1") (pintype "passive"))
      (node (ref "SCL") (pin "TP") (pinfunction "TP_TP") (pintype "input"))
      (node (ref "SERVO_DRIVER") (pin "26") (pinfunction "SCL_26") (pintype "bidirectional"))
      (node (ref "TEENSY4.1") (pin "19-A5/SCL0") (pinfunction "19-A5/SCL0_19-A5/SCL0") (pintype "bidirectional"))
      (node (ref "U1") (pin "SCK") (pinfunction "SCK_SCK") (pintype "bidirectional"))
    )
    (net (code "73") (name "SDA") (class "Default")
      (node (ref "IMU") (pin "SDA") (pinfunction "SDA_SDA") (pintype "bidirectional"))
      (node (ref "NAV") (pin "3") (pinfunction "3_3") (pintype "passive"))
      (node (ref "R33") (pin "1") (pinfunction "1_1") (pintype "passive"))
      (node (ref "SDA") (pin "TP") (pinfunction "TP_TP") (pintype "input"))
      (node (ref "SERVO_DRIVER") (pin "27") (pinfunction "SDA_27") (pintype "bidirectional"))
      (node (ref "TEENSY4.1") (pin "18-A4/SDA0") (pinfunction "18-A4/SDA0_18-A4/SDA0") (pintype "bidirectional"))
      (node (ref "U1") (pin "SDI") (pinfunction "SDI_SDI") (pintype "bidirectional"))
    )
    (net (code "74") (name "SELECT_PIN") (class "Default")
      (node (ref "NAV") (pin "2") (pinfunction "2_2") (pintype "passive"))
      (node (ref "R23") (pin "2") (pinfunction "2_2") (pintype "passive"))
      (node (ref "TEENSY4.1") (pin "31-CTX3") (pinfunction "31-CTX3_31-CTX3") (pintype "bidirectional"))
    )
    (net (code "75") (name "TX2") (class "Default")
      (node (ref "GPSMTK3339") (pin "RX") (pinfunction "RX_RX") (pintype "bidirectional"))
      (node (ref "TEENSY4.1") (pin "8-TX2/IN1") (pinfunction "8-TX2/IN1_8-TX2/IN1") (pintype "bidirectional"))
    )
    (net (code "76") (name "W_LED") (class "Default")
      (node (ref "TEENSY4.1") (pin "40-A16/CS1") (pinfunction "40-A16/CS1_40-A16/CS1") (pintype "bidirectional"))
      (node (ref "WHITE") (pin "1") (pinfunction "1_1") (pintype "passive"))
    )
    (net (code "77") (name "Y_LED") (class "Default")
      (node (ref "TEENSY4.1") (pin "39-A15/CS/OUT1A") (pinfunction "39-A15/CS/OUT1A_39-A15/CS/OUT1A") (pintype "bidirectional"))
      (node (ref "YELLOW") (pin "1") (pinfunction "1_1") (pintype "passive"))
    )
    (net (code "78") (name "unconnected-(AUX-Pad2)") (class "Default")
      (node (ref "AUX") (pin "2") (pinfunction "2_2") (pintype "passive"))
    )
    (net (code "79") (name "unconnected-(GPSMTK3339-Pad3.3V)") (class "Default")
      (node (ref "GPSMTK3339") (pin "3.3V") (pinfunction "3.3V_3.3V") (pintype "bidirectional"))
    )
    (net (code "80") (name "unconnected-(GPSMTK3339-PadVBAT)") (class "Default")
      (node (ref "GPSMTK3339") (pin "VBAT") (pinfunction "VBAT_VBAT") (pintype "bidirectional"))
    )
    (net (code "81") (name "unconnected-(IC3-COMP-Pad4)") (class "Default")
      (node (ref "IC3") (pin "4") (pinfunction "COMP_4") (pintype "bidirectional"))
    )
    (net (code "82") (name "unconnected-(IC3-EP-Pad9)") (class "Default")
      (node (ref "IC3") (pin "9") (pinfunction "EP_9") (pintype "bidirectional"))
    )
    (net (code "83") (name "unconnected-(IC3-SYNCH-Pad2)") (class "Default")
      (node (ref "IC3") (pin "2") (pinfunction "SYNCH_2") (pintype "bidirectional"))
    )
    (net (code "84") (name "unconnected-(RADIO-G1-Pad10)") (class "Default")
      (node (ref "RADIO") (pin "10") (pinfunction "G1_10") (pintype "bidirectional"))
    )
    (net (code "85") (name "unconnected-(RADIO-G2-Pad11)") (class "Default")
      (node (ref "RADIO") (pin "11") (pinfunction "G2_11") (pintype "bidirectional"))
    )
    (net (code "86") (name "unconnected-(RADIO-G3-Pad12)") (class "Default")
      (node (ref "RADIO") (pin "12") (pinfunction "G3_12") (pintype "bidirectional"))
    )
    (net (code "87") (name "unconnected-(RADIO-G4-Pad13)") (class "Default")
      (node (ref "RADIO") (pin "13") (pinfunction "G4_13") (pintype "bidirectional"))
    )
    (net (code "88") (name "unconnected-(RADIO-G5-Pad14)") (class "Default")
      (node (ref "RADIO") (pin "14") (pinfunction "G5_14") (pintype "bidirectional"))
    )
    (net (code "89") (name "unconnected-(TEENSY4.1-5V-Pad+5V)") (class "Default")
      (node (ref "TEENSY4.1") (pin "+5V") (pinfunction "5V_+5V") (pintype "bidirectional"))
    )
    (net (code "90") (name "unconnected-(TEENSY4.1-Pad0-RX1{slash}CS1{slash}CRX2)") (class "Default")
      (node (ref "TEENSY4.1") (pin "0-RX1/CS1/CRX2") (pinfunction "0-RX1/CS1/CRX2_0-RX1/CS1/CRX2") (pintype "bidirectional"))
    )
    (net (code "91") (name "unconnected-(TEENSY4.1-Pad1-TX1{slash}MISO1{slash}CTX2)") (class "Default")
      (node (ref "TEENSY4.1") (pin "1-TX1/MISO1/CTX2") (pinfunction "1-TX1/MISO1/CTX2_1-TX1/MISO1/CTX2") (pintype "bidirectional"))
    )
    (net (code "92") (name "unconnected-(TEENSY4.1-Pad2-OUT2)") (class "Default")
      (node (ref "TEENSY4.1") (pin "2-OUT2") (pinfunction "2-OUT2_2-OUT2") (pintype "bidirectional"))
    )
    (net (code "93") (name "unconnected-(TEENSY4.1-Pad6-OUT1D)") (class "Default")
      (node (ref "TEENSY4.1") (pin "6-OUT1D") (pinfunction "6-OUT1D_6-OUT1D") (pintype "bidirectional"))
    )
    (net (code "94") (name "unconnected-(TEENSY4.1-Pad16-A2{slash}RX4{slash}SCL1)") (class "Default")
      (node (ref "TEENSY4.1") (pin "16-A2/RX4/SCL1") (pinfunction "16-A2/RX4/SCL1_16-A2/RX4/SCL1") (pintype "bidirectional"))
    )
    (net (code "95") (name "unconnected-(TEENSY4.1-Pad17-A3{slash}TX4{slash}SDA1)") (class "Default")
      (node (ref "TEENSY4.1") (pin "17-A3/TX4/SDA1") (pinfunction "17-A3/TX4/SDA1_17-A3/TX4/SDA1") (pintype "bidirectional"))
    )
    (net (code "96") (name "unconnected-(TEENSY4.1-Pad20-A6{slash}TX5{slash}LRCLK1)") (class "Default")
      (node (ref "TEENSY4.1") (pin "20-A6/TX5/LRCLK1") (pinfunction "20-A6/TX5/LRCLK1_20-A6/TX5/LRCLK1") (pintype "bidirectional"))
    )
    (net (code "97") (name "unconnected-(TEENSY4.1-Pad21-A7{slash}RX5{slash}BCLK1)") (class "Default")
      (node (ref "TEENSY4.1") (pin "21-A7/RX5/BCLK1") (pinfunction "21-A7/RX5/BCLK1_21-A7/RX5/BCLK1") (pintype "bidirectional"))
    )
    (net (code "98") (name "unconnected-(TEENSY4.1-Pad23-A9{slash}CRX1{slash}MCLK1)") (class "Default")
      (node (ref "TEENSY4.1") (pin "23-A9/CRX1/MCLK1") (pinfunction "23-A9/CRX1/MCLK1_23-A9/CRX1/MCLK1") (pintype "bidirectional"))
    )
    (net (code "99") (name "unconnected-(TEENSY4.1-Pad24-A10{slash}TX6{slash}SCL2)") (class "Default")
      (node (ref "TEENSY4.1") (pin "24-A10/TX6/SCL2") (pinfunction "24-A10/TX6/SCL2_24-A10/TX6/SCL2") (pintype "bidirectional"))
    )
    (net (code "100") (name "unconnected-(TEENSY4.1-Pad25-A11{slash}RX6{slash}SDA2)") (class "Default")
      (node (ref "TEENSY4.1") (pin "25-A11/RX6/SDA2") (pinfunction "25-A11/RX6/SDA2_25-A11/RX6/SDA2") (pintype "bidirectional"))
    )
    (net (code "101") (name "unconnected-(TEENSY4.1-Pad28-RX7)") (class "Default")
      (node (ref "TEENSY4.1") (pin "28-RX7") (pinfunction "28-RX7_28-RX7") (pintype "bidirectional"))
    )
    (net (code "102") (name "unconnected-(TEENSY4.1-Pad29-TX7)") (class "Default")
      (node (ref "TEENSY4.1") (pin "29-TX7") (pinfunction "29-TX7_29-TX7") (pintype "bidirectional"))
    )
    (net (code "103") (name "unconnected-(TEENSY4.1-PadD+)") (class "Default")
      (node (ref "TEENSY4.1") (pin "D+") (pinfunction "D+_D+") (pintype "bidirectional"))
    )
    (net (code "104") (name "unconnected-(TEENSY4.1-PadD-)") (class "Default")
      (node (ref "TEENSY4.1") (pin "D-") (pinfunction "D-_D-") (pintype "bidirectional"))
    )
    (net (code "105") (name "unconnected-(TEENSY4.1-PadDM)") (class "Default")
      (node (ref "TEENSY4.1") (pin "DM") (pinfunction "DM_DM") (pintype "bidirectional"))
    )
    (net (code "106") (name "unconnected-(TEENSY4.1-PadDP)") (class "Default")
      (node (ref "TEENSY4.1") (pin "DP") (pinfunction "DP_DP") (pintype "bidirectional"))
    )
    (net (code "107") (name "unconnected-(TEENSY4.1-PadG)") (class "Default")
      (node (ref "TEENSY4.1") (pin "G") (pinfunction "G_G") (pintype "bidirectional"))
    )
    (net (code "108") (name "unconnected-(TEENSY4.1-PadLED)") (class "Default")
      (node (ref "TEENSY4.1") (pin "LED") (pinfunction "LED_LED") (pintype "bidirectional"))
    )
    (net (code "109") (name "unconnected-(TEENSY4.1-PadON{slash}OFF)") (class "Default")
      (node (ref "TEENSY4.1") (pin "ON/OFF") (pinfunction "ON/OFF_ON/OFF") (pintype "bidirectional"))
    )
    (net (code "110") (name "unconnected-(TEENSY4.1-PadPROGRAM)") (class "Default")
      (node (ref "TEENSY4.1") (pin "PROGRAM") (pinfunction "PROGRAM_PROGRAM") (pintype "bidirectional"))
    )
    (net (code "111") (name "unconnected-(TEENSY4.1-PadR+)") (class "Default")
      (node (ref "TEENSY4.1") (pin "R+") (pinfunction "R+_R+") (pintype "bidirectional"))
    )
    (net (code "112") (name "unconnected-(TEENSY4.1-PadR-)") (class "Default")
      (node (ref "TEENSY4.1") (pin "R-") (pinfunction "R-_R-") (pintype "bidirectional"))
    )
    (net (code "113") (name "unconnected-(TEENSY4.1-PadT+)") (class "Default")
      (node (ref "TEENSY4.1") (pin "T+") (pinfunction "T+_T+") (pintype "bidirectional"))
    )
    (net (code "114") (name "unconnected-(TEENSY4.1-PadT-)") (class "Default")
      (node (ref "TEENSY4.1") (pin "T-") (pinfunction "T-_T-") (pintype "bidirectional"))
    )
    (net (code "115") (name "unconnected-(TEENSY4.1-PadVBAT)") (class "Default")
      (node (ref "TEENSY4.1") (pin "VBAT") (pinfunction "VBAT_VBAT") (pintype "bidirectional"))
    )
    (net (code "116") (name "unconnected-(TEENSY4.1-PadVUSB)") (class "Default")
      (node (ref "TEENSY4.1") (pin "VUSB") (pinfunction "VUSB_VUSB") (pintype "bidirectional"))
    )
    (net (code "117") (name "unconnected-(U1-Pad3VO)") (class "Default")
      (node (ref "U1") (pin "3VO") (pinfunction "3VO_3VO") (pintype "bidirectional"))
    )
    (net (code "118") (name "unconnected-(U1-PadCS)") (class "Default")
      (node (ref "U1") (pin "CS") (pinfunction "CS_CS") (pintype "bidirectional"))
    )
    (net (code "119") (name "unconnected-(U1-PadSDO)") (class "Default")
      (node (ref "U1") (pin "SDO") (pinfunction "SDO_SDO") (pintype "bidirectional"))
    )
  )
)
